# ESP32_Sparrow.net
KiCad netlist of a schematic drawn in EAGLE
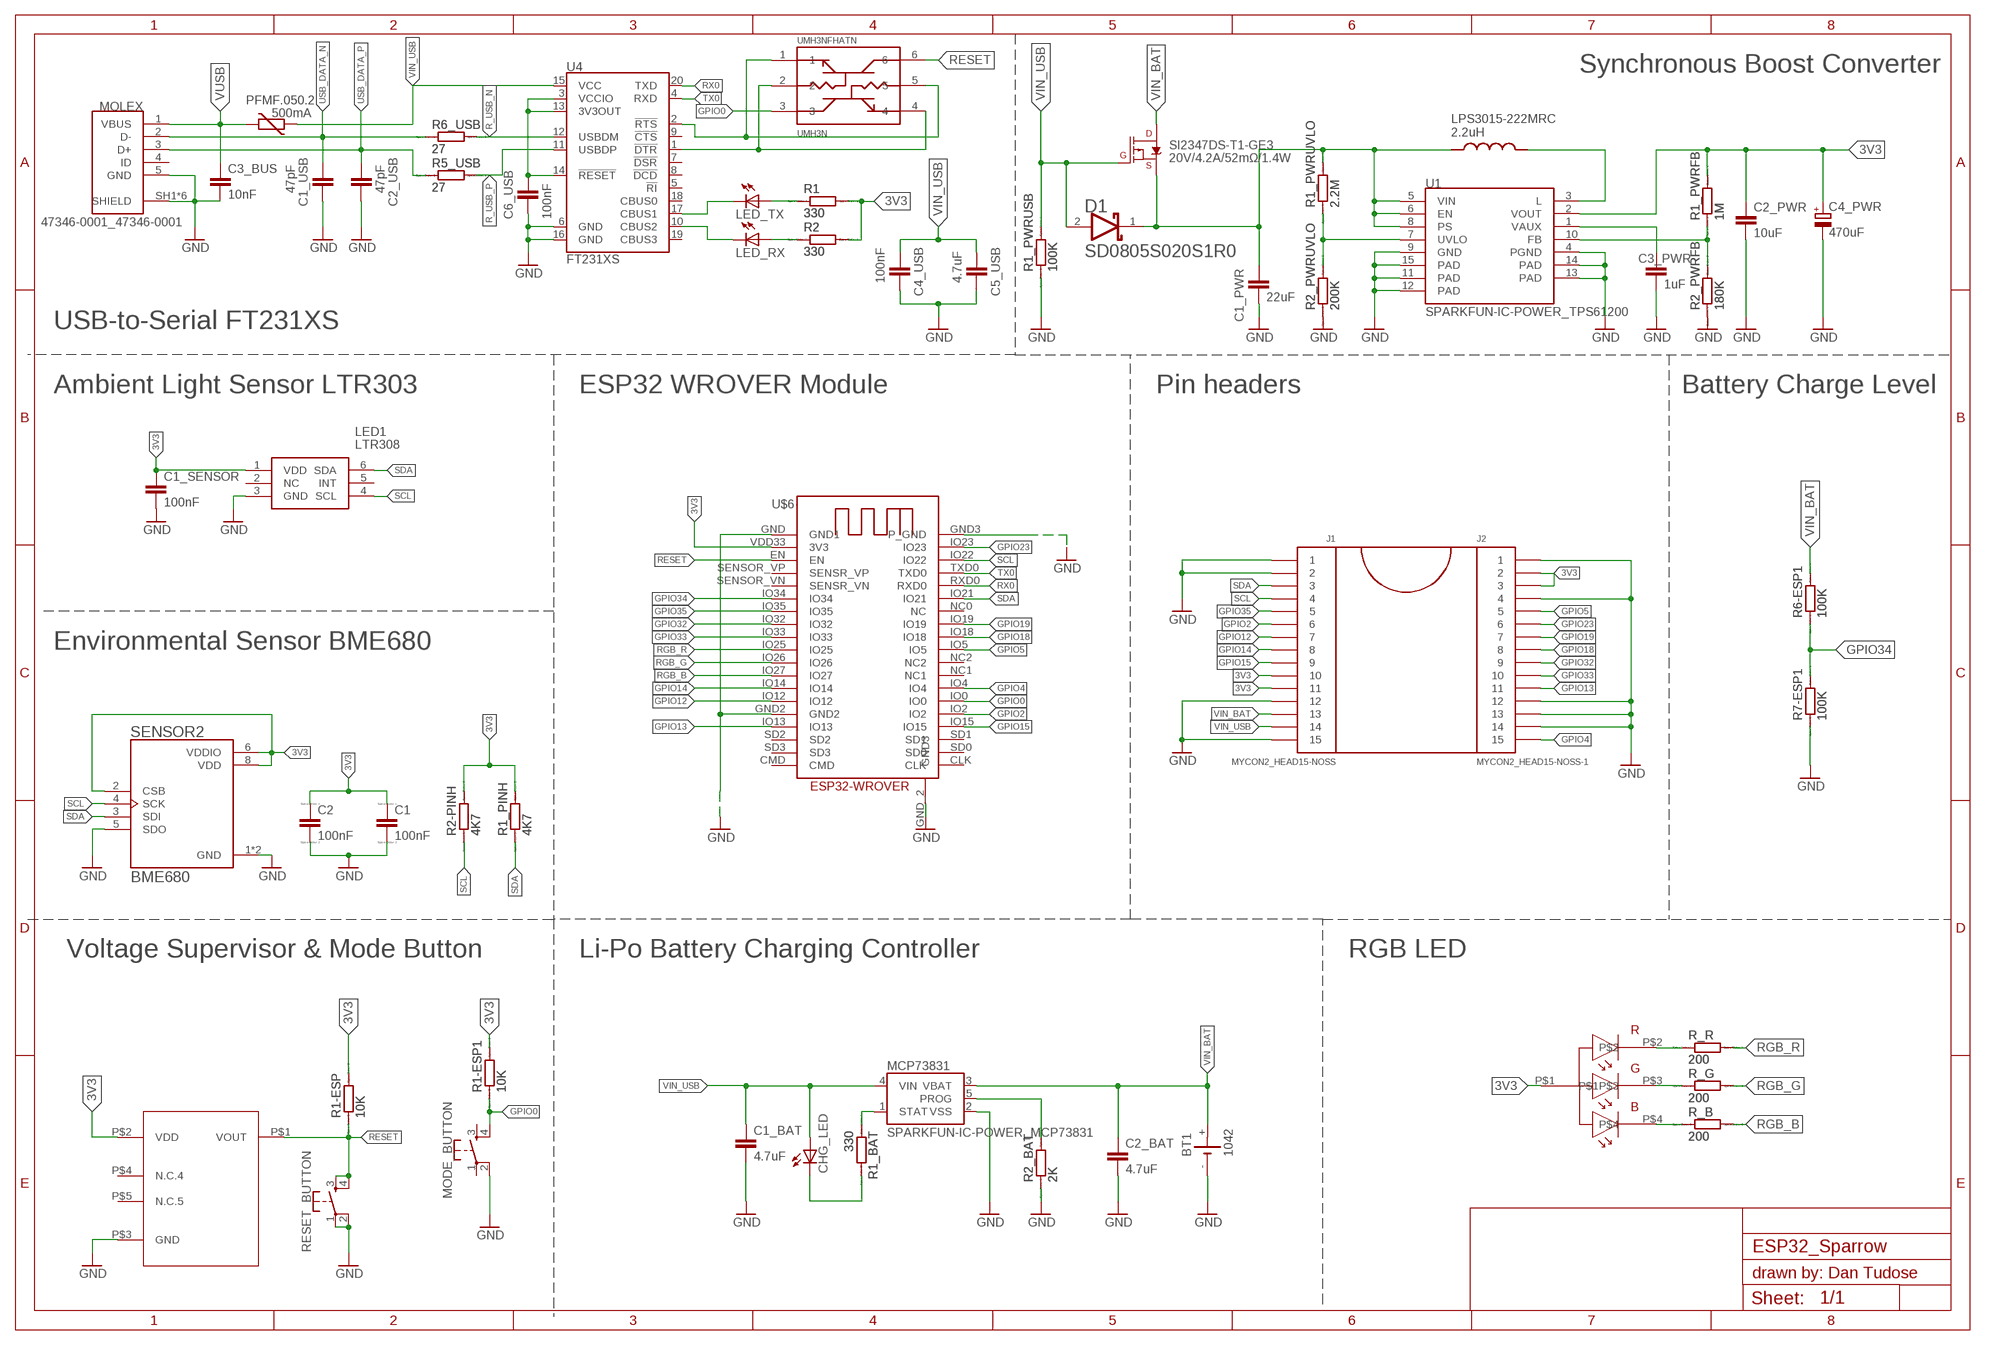
[diagram p0: schematic, sheet 1]

(export (version "E")
  (design (tool "Eeschema 10.0.6"))
  (components
    (comp (ref "BD48E27G-TR")
      (value "BD48E27G-TR_BD48E27G-TR")
      (footprint "eagle-import:BD48E27G-TR_SSOP5")
      (libsource (lib "eagle-import") (part "BD48E27G-TR_BD48E27G-TR"))
    )
    (comp (ref "BT1")
      (value "1042")
      (footprint "eagle-import:BAT_1042")
      (fields (field (name "MF") "Keystone Electronics Corp."))
      (libsource (lib "eagle-import") (part "1042"))
    )
    (comp (ref "C1")
      (value "100nF")
      (footprint "eagle-import:EAGLE-LTSPICE_C0402")
      (libsource (lib "eagle-import") (part "EAGLE-LTSPICE_CC0402"))
    )
    (comp (ref "C1_BAT")
      (value "4.7uF")
      (footprint "eagle-import:RCL_C0603")
      (libsource (lib "eagle-import") (part "RCL_C-EUC0603"))
    )
    (comp (ref "C1_PWR")
      (value "22uF")
      (footprint "eagle-import:RCL_C0603")
      (libsource (lib "eagle-import") (part "RCL_C-EUC0603"))
    )
    (comp (ref "C1_SENSOR")
      (value "100nF")
      (footprint "eagle-import:RCL_C0603")
      (libsource (lib "eagle-import") (part "RCL_C-EUC0603"))
    )
    (comp (ref "C1_USB")
      (value "47pF")
      (footprint "eagle-import:RCL_C0603")
      (libsource (lib "eagle-import") (part "RCL_C-EUC0603"))
    )
    (comp (ref "C2")
      (value "100nF")
      (footprint "eagle-import:EAGLE-LTSPICE_C0402")
      (libsource (lib "eagle-import") (part "EAGLE-LTSPICE_CC0402"))
    )
    (comp (ref "C2_BAT")
      (value "4.7uF")
      (footprint "eagle-import:RCL_C0603")
      (libsource (lib "eagle-import") (part "RCL_C-EUC0603"))
    )
    (comp (ref "C2_PWR")
      (value "10uF")
      (footprint "eagle-import:RCL_C0603")
      (libsource (lib "eagle-import") (part "RCL_C-EUC0603"))
    )
    (comp (ref "C2_USB")
      (value "47pF")
      (footprint "eagle-import:RCL_C0603")
      (libsource (lib "eagle-import") (part "RCL_C-EUC0603"))
    )
    (comp (ref "C3_BUS")
      (value "10nF")
      (footprint "eagle-import:RCL_C0603")
      (libsource (lib "eagle-import") (part "RCL_C-EUC0603"))
    )
    (comp (ref "C3_PWR")
      (value "1uF")
      (footprint "eagle-import:RCL_C0603")
      (libsource (lib "eagle-import") (part "RCL_C-EUC0603"))
    )
    (comp (ref "C4_PWR")
      (value "470uF")
      (footprint "eagle-import:RCL_D_7343-31R")
      (libsource (lib "eagle-import") (part "RCL_CPOL-EUD/7343-31R"))
    )
    (comp (ref "C4_USB")
      (value "100nF")
      (footprint "eagle-import:RCL_C0603")
      (libsource (lib "eagle-import") (part "RCL_C-EUC0603"))
    )
    (comp (ref "C5_USB")
      (value "4.7uF")
      (footprint "eagle-import:RCL_C0603")
      (libsource (lib "eagle-import") (part "RCL_C-EUC0603"))
    )
    (comp (ref "C6_USB")
      (value "100nF")
      (footprint "eagle-import:RCL_C0603")
      (libsource (lib "eagle-import") (part "RCL_C-EUC0603"))
    )
    (comp (ref "CHG_LED")
      (value "ADAFRUIT_LEDCHIP-LED0603")
      (footprint "eagle-import:ADAFRUIT_CHIP-LED0603")
      (libsource (lib "eagle-import") (part "ADAFRUIT_LEDCHIP-LED0603"))
    )
    (comp (ref "D1")
      (value "AVX---SD0805S020S1R0_AVX_SD0805S020S1R0AVX_SD0805S020S1R0_0_0")
      (footprint "eagle-import:AVX---SD0805S020S1R0_AVX_SD0805S020S1R0_0")
      (fields
        (field (name "DIGIKEY_PART_NUMBER") "478-7800-1-ND")
        (field (name "MF") "AVX")
        (field (name "MOUSER_PART_NUMBER") "581-SD0805S020S1R0")
      )
      (libsource (lib "eagle-import") (part "AVX---SD0805S020S1R0_AVX_SD0805S020S1R0AVX_SD0805S020S1R0_0_0"))
    )
    (comp (ref "J1")
      (value "MYCON2_HEAD15-NOSS")
      (footprint "eagle-import:MYCON2_HEAD15-NOSS")
      (libsource (lib "eagle-import") (part "MYCON2_HEAD15-NOSS"))
    )
    (comp (ref "J2")
      (value "MYCON2_HEAD15-NOSS-1")
      (footprint "eagle-import:MYCON2_HEAD15-NOSS-1")
      (libsource (lib "eagle-import") (part "MYCON2_HEAD15-NOSS-1"))
    )
    (comp (ref "LED1")
      (value "LTR308")
      (footprint "eagle-import:SAMACSYS_PARTS_LTR303ALS01")
      (fields
        (field (name "ARROW_PART_NUMBER") "LTR-303ALS-01")
        (field (name "MOUSER_PART_NUMBER") "859-LTR-303ALS-01")
      )
      (libsource (lib "eagle-import") (part "SAMACSYS_PARTS_LTR-303ALS-01"))
    )
    (comp (ref "LED_RX")
      (value "ADAFRUIT_LEDCHIP-LED0603")
      (footprint "eagle-import:ADAFRUIT_CHIP-LED0603")
      (libsource (lib "eagle-import") (part "ADAFRUIT_LEDCHIP-LED0603"))
    )
    (comp (ref "LED_TX")
      (value "ADAFRUIT_LEDCHIP-LED0603")
      (footprint "eagle-import:ADAFRUIT_CHIP-LED0603")
      (libsource (lib "eagle-import") (part "ADAFRUIT_LEDCHIP-LED0603"))
    )
    (comp (ref "MCP73831")
      (value "SPARKFUN-IC-POWER_MCP73831")
      (footprint "eagle-import:SPARKFUN-IC-POWER_SOT23-5")
      (libsource (lib "eagle-import") (part "SPARKFUN-IC-POWER_MCP73831"))
    )
    (comp (ref "MODE_BUTTON")
      (value "SPARKFUN-SWITCHES_MOMENTARY-SWITCH-SPST-2-SMD-4.6X2.8MM")
      (footprint "eagle-import:SPARKFUN-SWITCHES_TACTILE_SWITCH_SMD_4.6X2.8MM")
      (libsource (lib "eagle-import") (part "SPARKFUN-SWITCHES_MOMENTARY-SWITCH-SPST-2-SMD-4.6X2.8MM"))
    )
    (comp (ref "MOLEX")
      (value "47346-0001_47346-0001")
      (footprint "eagle-import:47346-0001_MOLEX_47346-0001")
      (fields (field (name "MF") "Molex") (field (name "MP") "47346-0001"))
      (libsource (lib "eagle-import") (part "47346-0001_47346-0001"))
    )
    (comp (ref "PFMF.050.2")
      (value "500mA")
      (footprint "eagle-import:VARISTOR_CT_CN1812")
      (libsource (lib "eagle-import") (part "VARISTOR_VARISTORCN1812"))
    )
    (comp (ref "R1")
      (value "330")
      (footprint "eagle-import:EAGLE-LTSPICE_R0402")
      (libsource (lib "eagle-import") (part "EAGLE-LTSPICE_R?R0402"))
    )
    (comp (ref "R1-ESP")
      (value "10K")
      (footprint "eagle-import:EAGLE-LTSPICE_R0402")
      (libsource (lib "eagle-import") (part "EAGLE-LTSPICE_R?R0402"))
    )
    (comp (ref "R1-ESP1")
      (value "10K")
      (footprint "eagle-import:EAGLE-LTSPICE_R0402")
      (libsource (lib "eagle-import") (part "EAGLE-LTSPICE_RR0402"))
    )
    (comp (ref "R1_BAT")
      (value "330")
      (footprint "eagle-import:EAGLE-LTSPICE_R0402")
      (libsource (lib "eagle-import") (part "EAGLE-LTSPICE_R?R0402"))
    )
    (comp (ref "R1_PINH")
      (value "4K7")
      (footprint "eagle-import:EAGLE-LTSPICE_R0402")
      (libsource (lib "eagle-import") (part "EAGLE-LTSPICE_R?R0402"))
    )
    (comp (ref "R1_PWRFB")
      (value "1M")
      (footprint "eagle-import:EAGLE-LTSPICE_R0402")
      (libsource (lib "eagle-import") (part "EAGLE-LTSPICE_RR0402"))
    )
    (comp (ref "R1_PWRUSB")
      (value "100K")
      (footprint "eagle-import:EAGLE-LTSPICE_R0402")
      (libsource (lib "eagle-import") (part "EAGLE-LTSPICE_R?R0402"))
    )
    (comp (ref "R1_PWRUVLO")
      (value "2.2M")
      (footprint "eagle-import:EAGLE-LTSPICE_R0402")
      (libsource (lib "eagle-import") (part "EAGLE-LTSPICE_R?R0402"))
    )
    (comp (ref "R2")
      (value "330")
      (footprint "eagle-import:EAGLE-LTSPICE_R0402")
      (libsource (lib "eagle-import") (part "EAGLE-LTSPICE_R?R0402"))
    )
    (comp (ref "R2-PINH")
      (value "4K7")
      (footprint "eagle-import:EAGLE-LTSPICE_R0402")
      (libsource (lib "eagle-import") (part "EAGLE-LTSPICE_R?R0402"))
    )
    (comp (ref "R2_BAT")
      (value "2K")
      (footprint "eagle-import:EAGLE-LTSPICE_R0402")
      (libsource (lib "eagle-import") (part "EAGLE-LTSPICE_RR0402"))
    )
    (comp (ref "R2_PWRFB")
      (value "180K")
      (footprint "eagle-import:EAGLE-LTSPICE_R0402")
      (libsource (lib "eagle-import") (part "EAGLE-LTSPICE_RR0402"))
    )
    (comp (ref "R2_PWRUVLO")
      (value "200K")
      (footprint "eagle-import:EAGLE-LTSPICE_R0402")
      (libsource (lib "eagle-import") (part "EAGLE-LTSPICE_R?R0402"))
    )
    (comp (ref "R5_USB")
      (value "27")
      (footprint "eagle-import:EAGLE-LTSPICE_R0402")
      (libsource (lib "eagle-import") (part "EAGLE-LTSPICE_R?R0402"))
    )
    (comp (ref "R6-ESP1")
      (value "100K")
      (footprint "eagle-import:EAGLE-LTSPICE_R0402")
      (libsource (lib "eagle-import") (part "EAGLE-LTSPICE_R?R0402"))
    )
    (comp (ref "R6_USB")
      (value "27")
      (footprint "eagle-import:EAGLE-LTSPICE_R0402")
      (libsource (lib "eagle-import") (part "EAGLE-LTSPICE_R?R0402"))
    )
    (comp (ref "R7-ESP1")
      (value "100K")
      (footprint "eagle-import:EAGLE-LTSPICE_R0402")
      (libsource (lib "eagle-import") (part "EAGLE-LTSPICE_R?R0402"))
    )
    (comp (ref "RESET_BUTTON")
      (value "SPARKFUN-SWITCHES_MOMENTARY-SWITCH-SPST-2-SMD-4.6X2.8MM")
      (footprint "eagle-import:SPARKFUN-SWITCHES_TACTILE_SWITCH_SMD_4.6X2.8MM")
      (libsource (lib "eagle-import") (part "SPARKFUN-SWITCHES_MOMENTARY-SWITCH-SPST-2-SMD-4.6X2.8MM"))
    )
    (comp (ref "R_B")
      (value "200")
      (footprint "eagle-import:EAGLE-LTSPICE_R0402")
      (libsource (lib "eagle-import") (part "EAGLE-LTSPICE_R?R0402"))
    )
    (comp (ref "R_G")
      (value "200")
      (footprint "eagle-import:EAGLE-LTSPICE_R0402")
      (libsource (lib "eagle-import") (part "EAGLE-LTSPICE_R?R0402"))
    )
    (comp (ref "R_R")
      (value "200")
      (footprint "eagle-import:EAGLE-LTSPICE_R0402")
      (libsource (lib "eagle-import") (part "EAGLE-LTSPICE_R?R0402"))
    )
    (comp (ref "SENSOR2")
      (value "BME680")
      (footprint "eagle-import:BME680_PSON80P300X300X100-8N")
      (fields (field (name "MF") "Bosch Sensortec"))
      (libsource (lib "eagle-import") (part "BME680_BME680"))
    )
    (comp (ref "SI2347DS-T1-GE3")
      (value "20V/4.2A/52mΩ/1.4W")
      (footprint "eagle-import:SPARKFUN-DISCRETESEMI_SOT23-3")
      (libsource (lib "eagle-import") (part "SPARKFUN-DISCRETESEMI_MOSFET_PCH-DMG2305UX-7"))
    )
    (comp (ref "U$2")
      (value "150202M153130_150202M153130-RGB")
      (footprint "eagle-import:150202M153130_150202M153130")
      (libsource (lib "eagle-import") (part "150202M153130_150202M153130-RGB"))
    )
    (comp (ref "U$5")
      (value "LPS3015_LPS3015")
      (footprint "eagle-import:LPS3015_LPS3015-222MRC")
      (libsource (lib "eagle-import") (part "LPS3015_LPS3015"))
    )
    (comp (ref "U$6")
      (value "ESP32-WROVER_ESP32-WROVER")
      (footprint "eagle-import:ESP32-WROVER_ESP32-WROVER")
      (libsource (lib "eagle-import") (part "ESP32-WROVER_ESP32-WROVER"))
    )
    (comp (ref "U1")
      (value "SPARKFUN-IC-POWER_TPS61200")
      (footprint "eagle-import:SPARKFUN-IC-POWER_QFN-10_PAD")
      (libsource (lib "eagle-import") (part "SPARKFUN-IC-POWER_TPS61200"))
    )
    (comp (ref "U4")
      (value "FT231XS")
      (footprint "eagle-import:SPARKFUN-IC-COMMS_SSOP20_L")
      (libsource (lib "eagle-import") (part "SPARKFUN-IC-COMMS_FT231XS"))
    )
    (comp (ref "UMH3NFHATN")
      (value "UMH3N_UMH3N")
      (footprint "eagle-import:UMH3N_SOP65P210X100-6N")
      (fields (field (name "MF") "Rohm") (field (name "MP") "UMH3N"))
      (libsource (lib "eagle-import") (part "UMH3N_UMH3N"))
    )
  )
  (nets
    (net (code "1") (name "3V3") (class "Default")
      (node (ref "BD48E27G-TR") (pin "P$2") (pinfunction "VDD_P$2") (pintype "bidirectional"))
      (node (ref "C1") (pin "1") (pinfunction "1_1") (pintype "passive"))
      (node (ref "C1_SENSOR") (pin "1") (pinfunction "1_1") (pintype "passive"))
      (node (ref "C2") (pin "1") (pinfunction "1_1") (pintype "passive"))
      (node (ref "C2_PWR") (pin "1") (pinfunction "1_1") (pintype "passive"))
      (node (ref "C4_PWR") (pin "+") (pinfunction "+_+") (pintype "passive"))
      (node (ref "J1") (pin "10") (pinfunction "10_10") (pintype "passive"))
      (node (ref "J1") (pin "11") (pinfunction "11_11") (pintype "passive"))
      (node (ref "J2") (pin "2") (pinfunction "2_2") (pintype "passive"))
      (node (ref "J2") (pin "3") (pinfunction "3_3") (pintype "passive"))
      (node (ref "LED1") (pin "1") (pinfunction "VDD_1") (pintype "bidirectional"))
      (node (ref "R1") (pin "2") (pinfunction "2_2") (pintype "passive"))
      (node (ref "R1-ESP") (pin "2") (pinfunction "2_2") (pintype "passive"))
      (node (ref "R1-ESP1") (pin "2") (pinfunction "2_2") (pintype "passive"))
      (node (ref "R1_PINH") (pin "2") (pinfunction "2_2") (pintype "passive"))
      (node (ref "R1_PWRFB") (pin "2") (pinfunction "2_2") (pintype "passive"))
      (node (ref "R2") (pin "2") (pinfunction "2_2") (pintype "passive"))
      (node (ref "R2-PINH") (pin "2") (pinfunction "2_2") (pintype "passive"))
      (node (ref "SENSOR2") (pin "2") (pinfunction "CSB_2") (pintype "input"))
      (node (ref "SENSOR2") (pin "6") (pinfunction "VDDIO_6") (pintype "power_in"))
      (node (ref "SENSOR2") (pin "8") (pinfunction "VDD_8") (pintype "power_in"))
      (node (ref "U$2") (pin "P$1") (pinfunction "P$1_P$1") (pintype "bidirectional"))
      (node (ref "U$6") (pin "VDD33") (pinfunction "3V3_VDD33") (pintype "bidirectional"))
      (node (ref "U1") (pin "2") (pinfunction "VOUT_2") (pintype "passive"))
    )
    (net (code "2") (name "GND") (class "Default")
      (node (ref "BD48E27G-TR") (pin "P$3") (pinfunction "GND_P$3") (pintype "bidirectional"))
      (node (ref "BT1") (pin "-") (pinfunction "-_-") (pintype "passive"))
      (node (ref "C1") (pin "2") (pinfunction "2_2") (pintype "passive"))
      (node (ref "C1_BAT") (pin "2") (pinfunction "2_2") (pintype "passive"))
      (node (ref "C1_PWR") (pin "2") (pinfunction "2_2") (pintype "passive"))
      (node (ref "C1_SENSOR") (pin "2") (pinfunction "2_2") (pintype "passive"))
      (node (ref "C1_USB") (pin "2") (pinfunction "2_2") (pintype "passive"))
      (node (ref "C2") (pin "2") (pinfunction "2_2") (pintype "passive"))
      (node (ref "C2_BAT") (pin "2") (pinfunction "2_2") (pintype "passive"))
      (node (ref "C2_PWR") (pin "2") (pinfunction "2_2") (pintype "passive"))
      (node (ref "C2_USB") (pin "2") (pinfunction "2_2") (pintype "passive"))
      (node (ref "C3_BUS") (pin "2") (pinfunction "2_2") (pintype "passive"))
      (node (ref "C3_PWR") (pin "2") (pinfunction "2_2") (pintype "passive"))
      (node (ref "C4_PWR") (pin "-") (pinfunction "-_-") (pintype "passive"))
      (node (ref "C4_USB") (pin "2") (pinfunction "2_2") (pintype "passive"))
      (node (ref "C5_USB") (pin "2") (pinfunction "2_2") (pintype "passive"))
      (node (ref "C6_USB") (pin "2") (pinfunction "2_2") (pintype "passive"))
      (node (ref "J1") (pin "1") (pinfunction "1_1") (pintype "passive"))
      (node (ref "J1") (pin "12") (pinfunction "12_12") (pintype "passive"))
      (node (ref "J1") (pin "15") (pinfunction "15_15") (pintype "passive"))
      (node (ref "J1") (pin "2") (pinfunction "2_2") (pintype "passive"))
      (node (ref "J2") (pin "1") (pinfunction "1_1") (pintype "passive"))
      (node (ref "J2") (pin "12") (pinfunction "12_12") (pintype "passive"))
      (node (ref "J2") (pin "13") (pinfunction "13_13") (pintype "passive"))
      (node (ref "J2") (pin "14") (pinfunction "14_14") (pintype "passive"))
      (node (ref "J2") (pin "4") (pinfunction "4_4") (pintype "passive"))
      (node (ref "LED1") (pin "3") (pinfunction "GND_3") (pintype "bidirectional"))
      (node (ref "MCP73831") (pin "2") (pinfunction "VSS_2") (pintype "power_in"))
      (node (ref "MODE_BUTTON") (pin "2") (pinfunction "2_2") (pintype "passive"))
      (node (ref "MOLEX") (pin "5") (pinfunction "GND_5") (pintype "power_in"))
      (node (ref "MOLEX") (pin "SH1") (pinfunction "SHIELD_SH1") (pintype "passive"))
      (node (ref "MOLEX") (pin "SH2") (pinfunction "SHIELD_SH2") (pintype "passive"))
      (node (ref "MOLEX") (pin "SH3") (pinfunction "SHIELD_SH3") (pintype "passive"))
      (node (ref "MOLEX") (pin "SH4") (pinfunction "SHIELD_SH4") (pintype "passive"))
      (node (ref "MOLEX") (pin "SH5") (pinfunction "SHIELD_SH5") (pintype "passive"))
      (node (ref "MOLEX") (pin "SH6") (pinfunction "SHIELD_SH6") (pintype "passive"))
      (node (ref "R1_PWRUSB") (pin "1") (pinfunction "1_1") (pintype "passive"))
      (node (ref "R2_BAT") (pin "1") (pinfunction "1_1") (pintype "passive"))
      (node (ref "R2_PWRFB") (pin "1") (pinfunction "1_1") (pintype "passive"))
      (node (ref "R2_PWRUVLO") (pin "1") (pinfunction "1_1") (pintype "passive"))
      (node (ref "R7-ESP1") (pin "1") (pinfunction "1_1") (pintype "passive"))
      (node (ref "RESET_BUTTON") (pin "1") (pinfunction "1_1") (pintype "passive"))
      (node (ref "RESET_BUTTON") (pin "2") (pinfunction "2_2") (pintype "passive"))
      (node (ref "SENSOR2") (pin "1") (pinfunction "GND_1") (pintype "power_in"))
      (node (ref "SENSOR2") (pin "5") (pinfunction "SDO_5") (pintype "bidirectional"))
      (node (ref "SENSOR2") (pin "7") (pinfunction "GND_7") (pintype "power_in"))
      (node (ref "U$6") (pin "GND") (pinfunction "GND1_GND") (pintype "bidirectional"))
      (node (ref "U$6") (pin "GND2") (pinfunction "GND2_GND2") (pintype "bidirectional"))
      (node (ref "U$6") (pin "GND3") (pinfunction "P_GND_GND3") (pintype "bidirectional"))
      (node (ref "U$6") (pin "GND_2") (pinfunction "GND3_GND_2") (pintype "bidirectional"))
      (node (ref "U1") (pin "11") (pinfunction "PAD_11") (pintype "power_in"))
      (node (ref "U1") (pin "12") (pinfunction "PAD_12") (pintype "power_in"))
      (node (ref "U1") (pin "13") (pinfunction "PAD_13") (pintype "power_in"))
      (node (ref "U1") (pin "14") (pinfunction "PAD_14") (pintype "power_in"))
      (node (ref "U1") (pin "15") (pinfunction "PAD_15") (pintype "power_in"))
      (node (ref "U1") (pin "4") (pinfunction "PGND_4") (pintype "power_in"))
      (node (ref "U1") (pin "9") (pinfunction "GND_9") (pintype "power_in"))
      (node (ref "U4") (pin "16") (pinfunction "GND_16") (pintype "bidirectional"))
      (node (ref "U4") (pin "6") (pinfunction "GND_6") (pintype "bidirectional"))
    )
    (net (code "3") (name "GPIO0") (class "Default")
      (node (ref "MODE_BUTTON") (pin "4") (pinfunction "4_4") (pintype "passive"))
      (node (ref "R1-ESP1") (pin "1") (pinfunction "1_1") (pintype "passive"))
      (node (ref "U$6") (pin "IO0") (pinfunction "IO0_IO0") (pintype "bidirectional"))
      (node (ref "UMH3NFHATN") (pin "3") (pinfunction "3_3") (pintype "bidirectional"))
    )
    (net (code "4") (name "GPIO2") (class "Default")
      (node (ref "J1") (pin "6") (pinfunction "6_6") (pintype "passive"))
      (node (ref "U$6") (pin "IO2") (pinfunction "IO2_IO2") (pintype "bidirectional"))
    )
    (net (code "5") (name "GPIO4") (class "Default")
      (node (ref "J2") (pin "15") (pinfunction "15_15") (pintype "passive"))
      (node (ref "U$6") (pin "IO4") (pinfunction "IO4_IO4") (pintype "bidirectional"))
    )
    (net (code "6") (name "GPIO5") (class "Default")
      (node (ref "J2") (pin "5") (pinfunction "5_5") (pintype "passive"))
      (node (ref "U$6") (pin "IO5") (pinfunction "IO5_IO5") (pintype "bidirectional"))
    )
    (net (code "7") (name "GPIO12") (class "Default")
      (node (ref "J1") (pin "7") (pinfunction "7_7") (pintype "passive"))
      (node (ref "U$6") (pin "IO12") (pinfunction "IO12_IO12") (pintype "bidirectional"))
    )
    (net (code "8") (name "GPIO13") (class "Default")
      (node (ref "J2") (pin "11") (pinfunction "11_11") (pintype "passive"))
      (node (ref "U$6") (pin "IO13") (pinfunction "IO13_IO13") (pintype "bidirectional"))
    )
    (net (code "9") (name "GPIO14") (class "Default")
      (node (ref "J1") (pin "8") (pinfunction "8_8") (pintype "passive"))
      (node (ref "U$6") (pin "IO14") (pinfunction "IO14_IO14") (pintype "bidirectional"))
    )
    (net (code "10") (name "GPIO15") (class "Default")
      (node (ref "J1") (pin "9") (pinfunction "9_9") (pintype "passive"))
      (node (ref "U$6") (pin "IO15") (pinfunction "IO15_IO15") (pintype "bidirectional"))
    )
    (net (code "11") (name "GPIO18") (class "Default")
      (node (ref "J2") (pin "8") (pinfunction "8_8") (pintype "passive"))
      (node (ref "U$6") (pin "IO18") (pinfunction "IO18_IO18") (pintype "bidirectional"))
    )
    (net (code "12") (name "GPIO19") (class "Default")
      (node (ref "J2") (pin "7") (pinfunction "7_7") (pintype "passive"))
      (node (ref "U$6") (pin "IO19") (pinfunction "IO19_IO19") (pintype "bidirectional"))
    )
    (net (code "13") (name "GPIO23") (class "Default")
      (node (ref "J2") (pin "6") (pinfunction "6_6") (pintype "passive"))
      (node (ref "U$6") (pin "IO23") (pinfunction "IO23_IO23") (pintype "bidirectional"))
    )
    (net (code "14") (name "GPIO32") (class "Default")
      (node (ref "J2") (pin "9") (pinfunction "9_9") (pintype "passive"))
      (node (ref "U$6") (pin "IO32") (pinfunction "IO32_IO32") (pintype "bidirectional"))
    )
    (net (code "15") (name "GPIO33") (class "Default")
      (node (ref "J2") (pin "10") (pinfunction "10_10") (pintype "passive"))
      (node (ref "U$6") (pin "IO33") (pinfunction "IO33_IO33") (pintype "bidirectional"))
    )
    (net (code "16") (name "GPIO34") (class "Default")
      (node (ref "R6-ESP1") (pin "1") (pinfunction "1_1") (pintype "passive"))
      (node (ref "R7-ESP1") (pin "2") (pinfunction "2_2") (pintype "passive"))
      (node (ref "U$6") (pin "IO34") (pinfunction "IO34_IO34") (pintype "bidirectional"))
    )
    (net (code "17") (name "GPIO35") (class "Default")
      (node (ref "J1") (pin "5") (pinfunction "5_5") (pintype "passive"))
      (node (ref "U$6") (pin "IO35") (pinfunction "IO35_IO35") (pintype "bidirectional"))
    )
    (net (code "18") (name "Net-(CHG_LED-PadC)") (class "Default")
      (node (ref "CHG_LED") (pin "C") (pinfunction "C_C") (pintype "passive"))
      (node (ref "R1_BAT") (pin "2") (pinfunction "2_2") (pintype "passive"))
    )
    (net (code "19") (name "Net-(D1-CATHODE)") (class "Default")
      (node (ref "C1_PWR") (pin "1") (pinfunction "1_1") (pintype "passive"))
      (node (ref "D1") (pin "1") (pinfunction "CATHODE_1") (pintype "bidirectional"))
      (node (ref "R1_PWRUVLO") (pin "2") (pinfunction "2_2") (pintype "passive"))
      (node (ref "SI2347DS-T1-GE3") (pin "2") (pinfunction "S_2") (pintype "bidirectional"))
      (node (ref "U$5") (pin "P$1") (pinfunction "P$1_P$1") (pintype "bidirectional"))
      (node (ref "U1") (pin "5") (pinfunction "VIN_5") (pintype "power_in"))
      (node (ref "U1") (pin "6") (pinfunction "EN_6") (pintype "input"))
      (node (ref "U1") (pin "8") (pinfunction "PS_8") (pintype "input"))
    )
    (net (code "20") (name "Net-(LED_RX-PadA)") (class "Default")
      (node (ref "LED_RX") (pin "A") (pinfunction "A_A") (pintype "passive"))
      (node (ref "R2") (pin "1") (pinfunction "1_1") (pintype "passive"))
    )
    (net (code "21") (name "Net-(LED_TX-PadA)") (class "Default")
      (node (ref "LED_TX") (pin "A") (pinfunction "A_A") (pintype "passive"))
      (node (ref "R1") (pin "1") (pinfunction "1_1") (pintype "passive"))
    )
    (net (code "22") (name "Net-(MCP73831-PROG)") (class "Default")
      (node (ref "MCP73831") (pin "5") (pinfunction "PROG_5") (pintype "input"))
      (node (ref "R2_BAT") (pin "2") (pinfunction "2_2") (pintype "passive"))
    )
    (net (code "23") (name "Net-(MCP73831-STAT)") (class "Default")
      (node (ref "MCP73831") (pin "1") (pinfunction "STAT_1") (pintype "output"))
      (node (ref "R1_BAT") (pin "1") (pinfunction "1_1") (pintype "passive"))
    )
    (net (code "24") (name "Net-(R_B-Pad1)") (class "Default")
      (node (ref "R_B") (pin "1") (pinfunction "1_1") (pintype "passive"))
      (node (ref "U$2") (pin "P$4") (pinfunction "P$4_P$4") (pintype "bidirectional"))
    )
    (net (code "25") (name "Net-(R_G-Pad1)") (class "Default")
      (node (ref "R_G") (pin "1") (pinfunction "1_1") (pintype "passive"))
      (node (ref "U$2") (pin "P$3") (pinfunction "P$3_P$3") (pintype "bidirectional"))
    )
    (net (code "26") (name "Net-(R_R-Pad1)") (class "Default")
      (node (ref "R_R") (pin "1") (pinfunction "1_1") (pintype "passive"))
      (node (ref "U$2") (pin "P$2") (pinfunction "P$2_P$2") (pintype "bidirectional"))
    )
    (net (code "27") (name "Net-(U1-FB)") (class "Default")
      (node (ref "R1_PWRFB") (pin "1") (pinfunction "1_1") (pintype "passive"))
      (node (ref "R2_PWRFB") (pin "2") (pinfunction "2_2") (pintype "passive"))
      (node (ref "U1") (pin "10") (pinfunction "FB_10") (pintype "passive"))
    )
    (net (code "28") (name "Net-(U1-L)") (class "Default")
      (node (ref "U$5") (pin "P$2") (pinfunction "P$2_P$2") (pintype "bidirectional"))
      (node (ref "U1") (pin "3") (pinfunction "L_3") (pintype "passive"))
    )
    (net (code "29") (name "Net-(U1-UVLO)") (class "Default")
      (node (ref "R1_PWRUVLO") (pin "1") (pinfunction "1_1") (pintype "passive"))
      (node (ref "R2_PWRUVLO") (pin "2") (pinfunction "2_2") (pintype "passive"))
      (node (ref "U1") (pin "7") (pinfunction "UVLO_7") (pintype "passive"))
    )
    (net (code "30") (name "Net-(U1-VAUX)") (class "Default")
      (node (ref "C3_PWR") (pin "1") (pinfunction "1_1") (pintype "passive"))
      (node (ref "U1") (pin "1") (pinfunction "VAUX_1") (pintype "passive"))
    )
    (net (code "31") (name "Net-(U4-3V3OUT)") (class "Default")
      (node (ref "C6_USB") (pin "1") (pinfunction "1_1") (pintype "passive"))
      (node (ref "U4") (pin "13") (pinfunction "3V3OUT_13") (pintype "bidirectional"))
      (node (ref "U4") (pin "14") (pinfunction "~{RESET}_14") (pintype "bidirectional"))
      (node (ref "U4") (pin "3") (pinfunction "VCCIO_3") (pintype "bidirectional"))
    )
    (net (code "32") (name "Net-(U4-CBUS1)") (class "Default")
      (node (ref "LED_TX") (pin "C") (pinfunction "C_C") (pintype "passive"))
      (node (ref "U4") (pin "17") (pinfunction "CBUS1_17") (pintype "bidirectional"))
    )
    (net (code "33") (name "Net-(U4-CBUS2)") (class "Default")
      (node (ref "LED_RX") (pin "C") (pinfunction "C_C") (pintype "passive"))
      (node (ref "U4") (pin "10") (pinfunction "CBUS2_10") (pintype "bidirectional"))
    )
    (net (code "34") (name "Net-(U4-~{DTR})") (class "Default")
      (node (ref "U4") (pin "1") (pinfunction "~{DTR}_1") (pintype "bidirectional"))
      (node (ref "UMH3NFHATN") (pin "2") (pinfunction "2_2") (pintype "bidirectional"))
      (node (ref "UMH3NFHATN") (pin "4") (pinfunction "4_4") (pintype "bidirectional"))
    )
    (net (code "35") (name "Net-(U4-~{RTS})") (class "Default")
      (node (ref "U4") (pin "2") (pinfunction "~{RTS}_2") (pintype "bidirectional"))
      (node (ref "UMH3NFHATN") (pin "1") (pinfunction "1_1") (pintype "bidirectional"))
      (node (ref "UMH3NFHATN") (pin "5") (pinfunction "5_5") (pintype "bidirectional"))
    )
    (net (code "36") (name "RESET") (class "Default")
      (node (ref "BD48E27G-TR") (pin "P$1") (pinfunction "VOUT_P$1") (pintype "bidirectional"))
      (node (ref "R1-ESP") (pin "1") (pinfunction "1_1") (pintype "passive"))
      (node (ref "RESET_BUTTON") (pin "3") (pinfunction "3_3") (pintype "passive"))
      (node (ref "RESET_BUTTON") (pin "4") (pinfunction "4_4") (pintype "passive"))
      (node (ref "U$6") (pin "EN") (pinfunction "EN_EN") (pintype "bidirectional"))
      (node (ref "UMH3NFHATN") (pin "6") (pinfunction "6_6") (pintype "bidirectional"))
    )
    (net (code "37") (name "RGB_B") (class "Default")
      (node (ref "R_B") (pin "2") (pinfunction "2_2") (pintype "passive"))
      (node (ref "U$6") (pin "IO27") (pinfunction "IO27_IO27") (pintype "bidirectional"))
    )
    (net (code "38") (name "RGB_G") (class "Default")
      (node (ref "R_G") (pin "2") (pinfunction "2_2") (pintype "passive"))
      (node (ref "U$6") (pin "IO26") (pinfunction "IO26_IO26") (pintype "bidirectional"))
    )
    (net (code "39") (name "RGB_R") (class "Default")
      (node (ref "R_R") (pin "2") (pinfunction "2_2") (pintype "passive"))
      (node (ref "U$6") (pin "IO25") (pinfunction "IO25_IO25") (pintype "bidirectional"))
    )
    (net (code "40") (name "RX0") (class "Default")
      (node (ref "U$6") (pin "RXD0") (pinfunction "RXD0_RXD0") (pintype "bidirectional"))
      (node (ref "U4") (pin "20") (pinfunction "TXD_20") (pintype "bidirectional"))
    )
    (net (code "41") (name "R_USB_N") (class "Default")
      (node (ref "R6_USB") (pin "2") (pinfunction "2_2") (pintype "passive"))
      (node (ref "U4") (pin "12") (pinfunction "USBDM_12") (pintype "bidirectional"))
    )
    (net (code "42") (name "R_USB_P") (class "Default")
      (node (ref "R5_USB") (pin "2") (pinfunction "2_2") (pintype "passive"))
      (node (ref "U4") (pin "11") (pinfunction "USBDP_11") (pintype "bidirectional"))
    )
    (net (code "43") (name "SCL") (class "Default")
      (node (ref "J1") (pin "4") (pinfunction "4_4") (pintype "passive"))
      (node (ref "LED1") (pin "4") (pinfunction "SCL_4") (pintype "bidirectional"))
      (node (ref "R2-PINH") (pin "1") (pinfunction "1_1") (pintype "passive"))
      (node (ref "SENSOR2") (pin "4") (pinfunction "SCK_4") (pintype "input"))
      (node (ref "U$6") (pin "IO22") (pinfunction "IO22_IO22") (pintype "bidirectional"))
    )
    (net (code "44") (name "SDA") (class "Default")
      (node (ref "J1") (pin "3") (pinfunction "3_3") (pintype "passive"))
      (node (ref "LED1") (pin "6") (pinfunction "SDA_6") (pintype "bidirectional"))
      (node (ref "R1_PINH") (pin "1") (pinfunction "1_1") (pintype "passive"))
      (node (ref "SENSOR2") (pin "3") (pinfunction "SDI_3") (pintype "bidirectional"))
      (node (ref "U$6") (pin "IO21") (pinfunction "IO21_IO21") (pintype "bidirectional"))
    )
    (net (code "45") (name "TX0") (class "Default")
      (node (ref "U$6") (pin "TXD0") (pinfunction "TXD0_TXD0") (pintype "bidirectional"))
      (node (ref "U4") (pin "4") (pinfunction "RXD_4") (pintype "bidirectional"))
    )
    (net (code "46") (name "USB_DATA_N") (class "Default")
      (node (ref "C1_USB") (pin "1") (pinfunction "1_1") (pintype "passive"))
      (node (ref "MOLEX") (pin "2") (pinfunction "D-_2") (pintype "bidirectional"))
      (node (ref "R6_USB") (pin "1") (pinfunction "1_1") (pintype "passive"))
    )
    (net (code "47") (name "USB_DATA_P") (class "Default")
      (node (ref "C2_USB") (pin "1") (pinfunction "1_1") (pintype "passive"))
      (node (ref "MOLEX") (pin "3") (pinfunction "D+_3") (pintype "bidirectional"))
      (node (ref "R5_USB") (pin "1") (pinfunction "1_1") (pintype "passive"))
    )
    (net (code "48") (name "VIN_BAT") (class "Default")
      (node (ref "BT1") (pin "+") (pinfunction "+_+") (pintype "passive"))
      (node (ref "C2_BAT") (pin "1") (pinfunction "1_1") (pintype "passive"))
      (node (ref "J1") (pin "13") (pinfunction "13_13") (pintype "passive"))
      (node (ref "MCP73831") (pin "3") (pinfunction "VBAT_3") (pintype "power_in"))
      (node (ref "R6-ESP1") (pin "2") (pinfunction "2_2") (pintype "passive"))
      (node (ref "SI2347DS-T1-GE3") (pin "3") (pinfunction "D_3") (pintype "bidirectional"))
    )
    (net (code "49") (name "VIN_USB") (class "Default")
      (node (ref "C1_BAT") (pin "1") (pinfunction "1_1") (pintype "passive"))
      (node (ref "C4_USB") (pin "1") (pinfunction "1_1") (pintype "passive"))
      (node (ref "C5_USB") (pin "1") (pinfunction "1_1") (pintype "passive"))
      (node (ref "CHG_LED") (pin "A") (pinfunction "A_A") (pintype "passive"))
      (node (ref "D1") (pin "2") (pinfunction "ANODE_2") (pintype "bidirectional"))
      (node (ref "J1") (pin "14") (pinfunction "14_14") (pintype "passive"))
      (node (ref "MCP73831") (pin "4") (pinfunction "VIN_4") (pintype "power_in"))
      (node (ref "PFMF.050.2") (pin "1") (pinfunction "1_1") (pintype "passive"))
      (node (ref "R1_PWRUSB") (pin "2") (pinfunction "2_2") (pintype "passive"))
      (node (ref "SI2347DS-T1-GE3") (pin "1") (pinfunction "G_1") (pintype "bidirectional"))
      (node (ref "U4") (pin "15") (pinfunction "VCC_15") (pintype "bidirectional"))
    )
    (net (code "50") (name "VUSB") (class "Default")
      (node (ref "C3_BUS") (pin "1") (pinfunction "1_1") (pintype "passive"))
      (node (ref "MOLEX") (pin "1") (pinfunction "VBUS_1") (pintype "power_in"))
      (node (ref "PFMF.050.2") (pin "2") (pinfunction "2_2") (pintype "passive"))
    )
    (net (code "51") (name "unconnected-(BD48E27G-TR-N.C.4-PadP$4)") (class "Default")
      (node (ref "BD48E27G-TR") (pin "P$4") (pinfunction "N.C.4_P$4") (pintype "bidirectional"))
    )
    (net (code "52") (name "unconnected-(BD48E27G-TR-N.C.5-PadP$5)") (class "Default")
      (node (ref "BD48E27G-TR") (pin "P$5") (pinfunction "N.C.5_P$5") (pintype "bidirectional"))
    )
    (net (code "53") (name "unconnected-(LED1-INT-Pad5)") (class "Default")
      (node (ref "LED1") (pin "5") (pinfunction "INT_5") (pintype "bidirectional"))
    )
    (net (code "54") (name "unconnected-(LED1-NC-Pad2)") (class "Default")
      (node (ref "LED1") (pin "2") (pinfunction "NC_2") (pintype "no_connect"))
    )
    (net (code "55") (name "unconnected-(MODE_BUTTON-Pad1)") (class "Default")
      (node (ref "MODE_BUTTON") (pin "1") (pinfunction "1_1") (pintype "passive"))
    )
    (net (code "56") (name "unconnected-(MODE_BUTTON-Pad3)") (class "Default")
      (node (ref "MODE_BUTTON") (pin "3") (pinfunction "3_3") (pintype "passive"))
    )
    (net (code "57") (name "unconnected-(MOLEX-ID-Pad4)") (class "Default")
      (node (ref "MOLEX") (pin "4") (pinfunction "ID_4") (pintype "passive"))
    )
    (net (code "58") (name "unconnected-(U$6-NC-PadNC0)") (class "Default")
      (node (ref "U$6") (pin "NC0") (pinfunction "NC_NC0") (pintype "bidirectional"))
    )
    (net (code "59") (name "unconnected-(U$6-PadCLK)") (class "Default")
      (node (ref "U$6") (pin "CLK") (pinfunction "CLK_CLK") (pintype "bidirectional"))
    )
    (net (code "60") (name "unconnected-(U$6-PadCMD)") (class "Default")
      (node (ref "U$6") (pin "CMD") (pinfunction "CMD_CMD") (pintype "bidirectional"))
    )
    (net (code "61") (name "unconnected-(U$6-PadNC1)") (class "Default")
      (node (ref "U$6") (pin "NC1") (pinfunction "NC1_NC1") (pintype "bidirectional"))
    )
    (net (code "62") (name "unconnected-(U$6-PadNC2)") (class "Default")
      (node (ref "U$6") (pin "NC2") (pinfunction "NC2_NC2") (pintype "bidirectional"))
    )
    (net (code "63") (name "unconnected-(U$6-PadSD0)") (class "Default")
      (node (ref "U$6") (pin "SD0") (pinfunction "SD0_SD0") (pintype "bidirectional"))
    )
    (net (code "64") (name "unconnected-(U$6-PadSD1)") (class "Default")
      (node (ref "U$6") (pin "SD1") (pinfunction "SD1_SD1") (pintype "bidirectional"))
    )
    (net (code "65") (name "unconnected-(U$6-PadSD2)") (class "Default")
      (node (ref "U$6") (pin "SD2") (pinfunction "SD2_SD2") (pintype "bidirectional"))
    )
    (net (code "66") (name "unconnected-(U$6-PadSD3)") (class "Default")
      (node (ref "U$6") (pin "SD3") (pinfunction "SD3_SD3") (pintype "bidirectional"))
    )
    (net (code "67") (name "unconnected-(U$6-SENSR_VN-PadSENSOR_VN)") (class "Default")
      (node (ref "U$6") (pin "SENSOR_VN") (pinfunction "SENSR_VN_SENSOR_VN") (pintype "bidirectional"))
    )
    (net (code "68") (name "unconnected-(U$6-SENSR_VP-PadSENSOR_VP)") (class "Default")
      (node (ref "U$6") (pin "SENSOR_VP") (pinfunction "SENSR_VP_SENSOR_VP") (pintype "bidirectional"))
    )
    (net (code "69") (name "unconnected-(U4-CBUS0-Pad18)") (class "Default")
      (node (ref "U4") (pin "18") (pinfunction "CBUS0_18") (pintype "bidirectional"))
    )
    (net (code "70") (name "unconnected-(U4-CBUS3-Pad19)") (class "Default")
      (node (ref "U4") (pin "19") (pinfunction "CBUS3_19") (pintype "bidirectional"))
    )
    (net (code "71") (name "unconnected-(U4-~{CTS}-Pad9)") (class "Default")
      (node (ref "U4") (pin "9") (pinfunction "~{CTS}_9") (pintype "bidirectional"))
    )
    (net (code "72") (name "unconnected-(U4-~{DCD}-Pad8)") (class "Default")
      (node (ref "U4") (pin "8") (pinfunction "~{DCD}_8") (pintype "bidirectional"))
    )
    (net (code "73") (name "unconnected-(U4-~{DSR}-Pad7)") (class "Default")
      (node (ref "U4") (pin "7") (pinfunction "~{DSR}_7") (pintype "bidirectional"))
    )
    (net (code "74") (name "unconnected-(U4-~{RI}-Pad5)") (class "Default")
      (node (ref "U4") (pin "5") (pinfunction "~{RI}_5") (pintype "bidirectional"))
    )
  )
)
